# ProDocument_N64_SpyDVI_2024-08-21.net
KiCad netlist of a schematic drawn in EasyEDA Pro
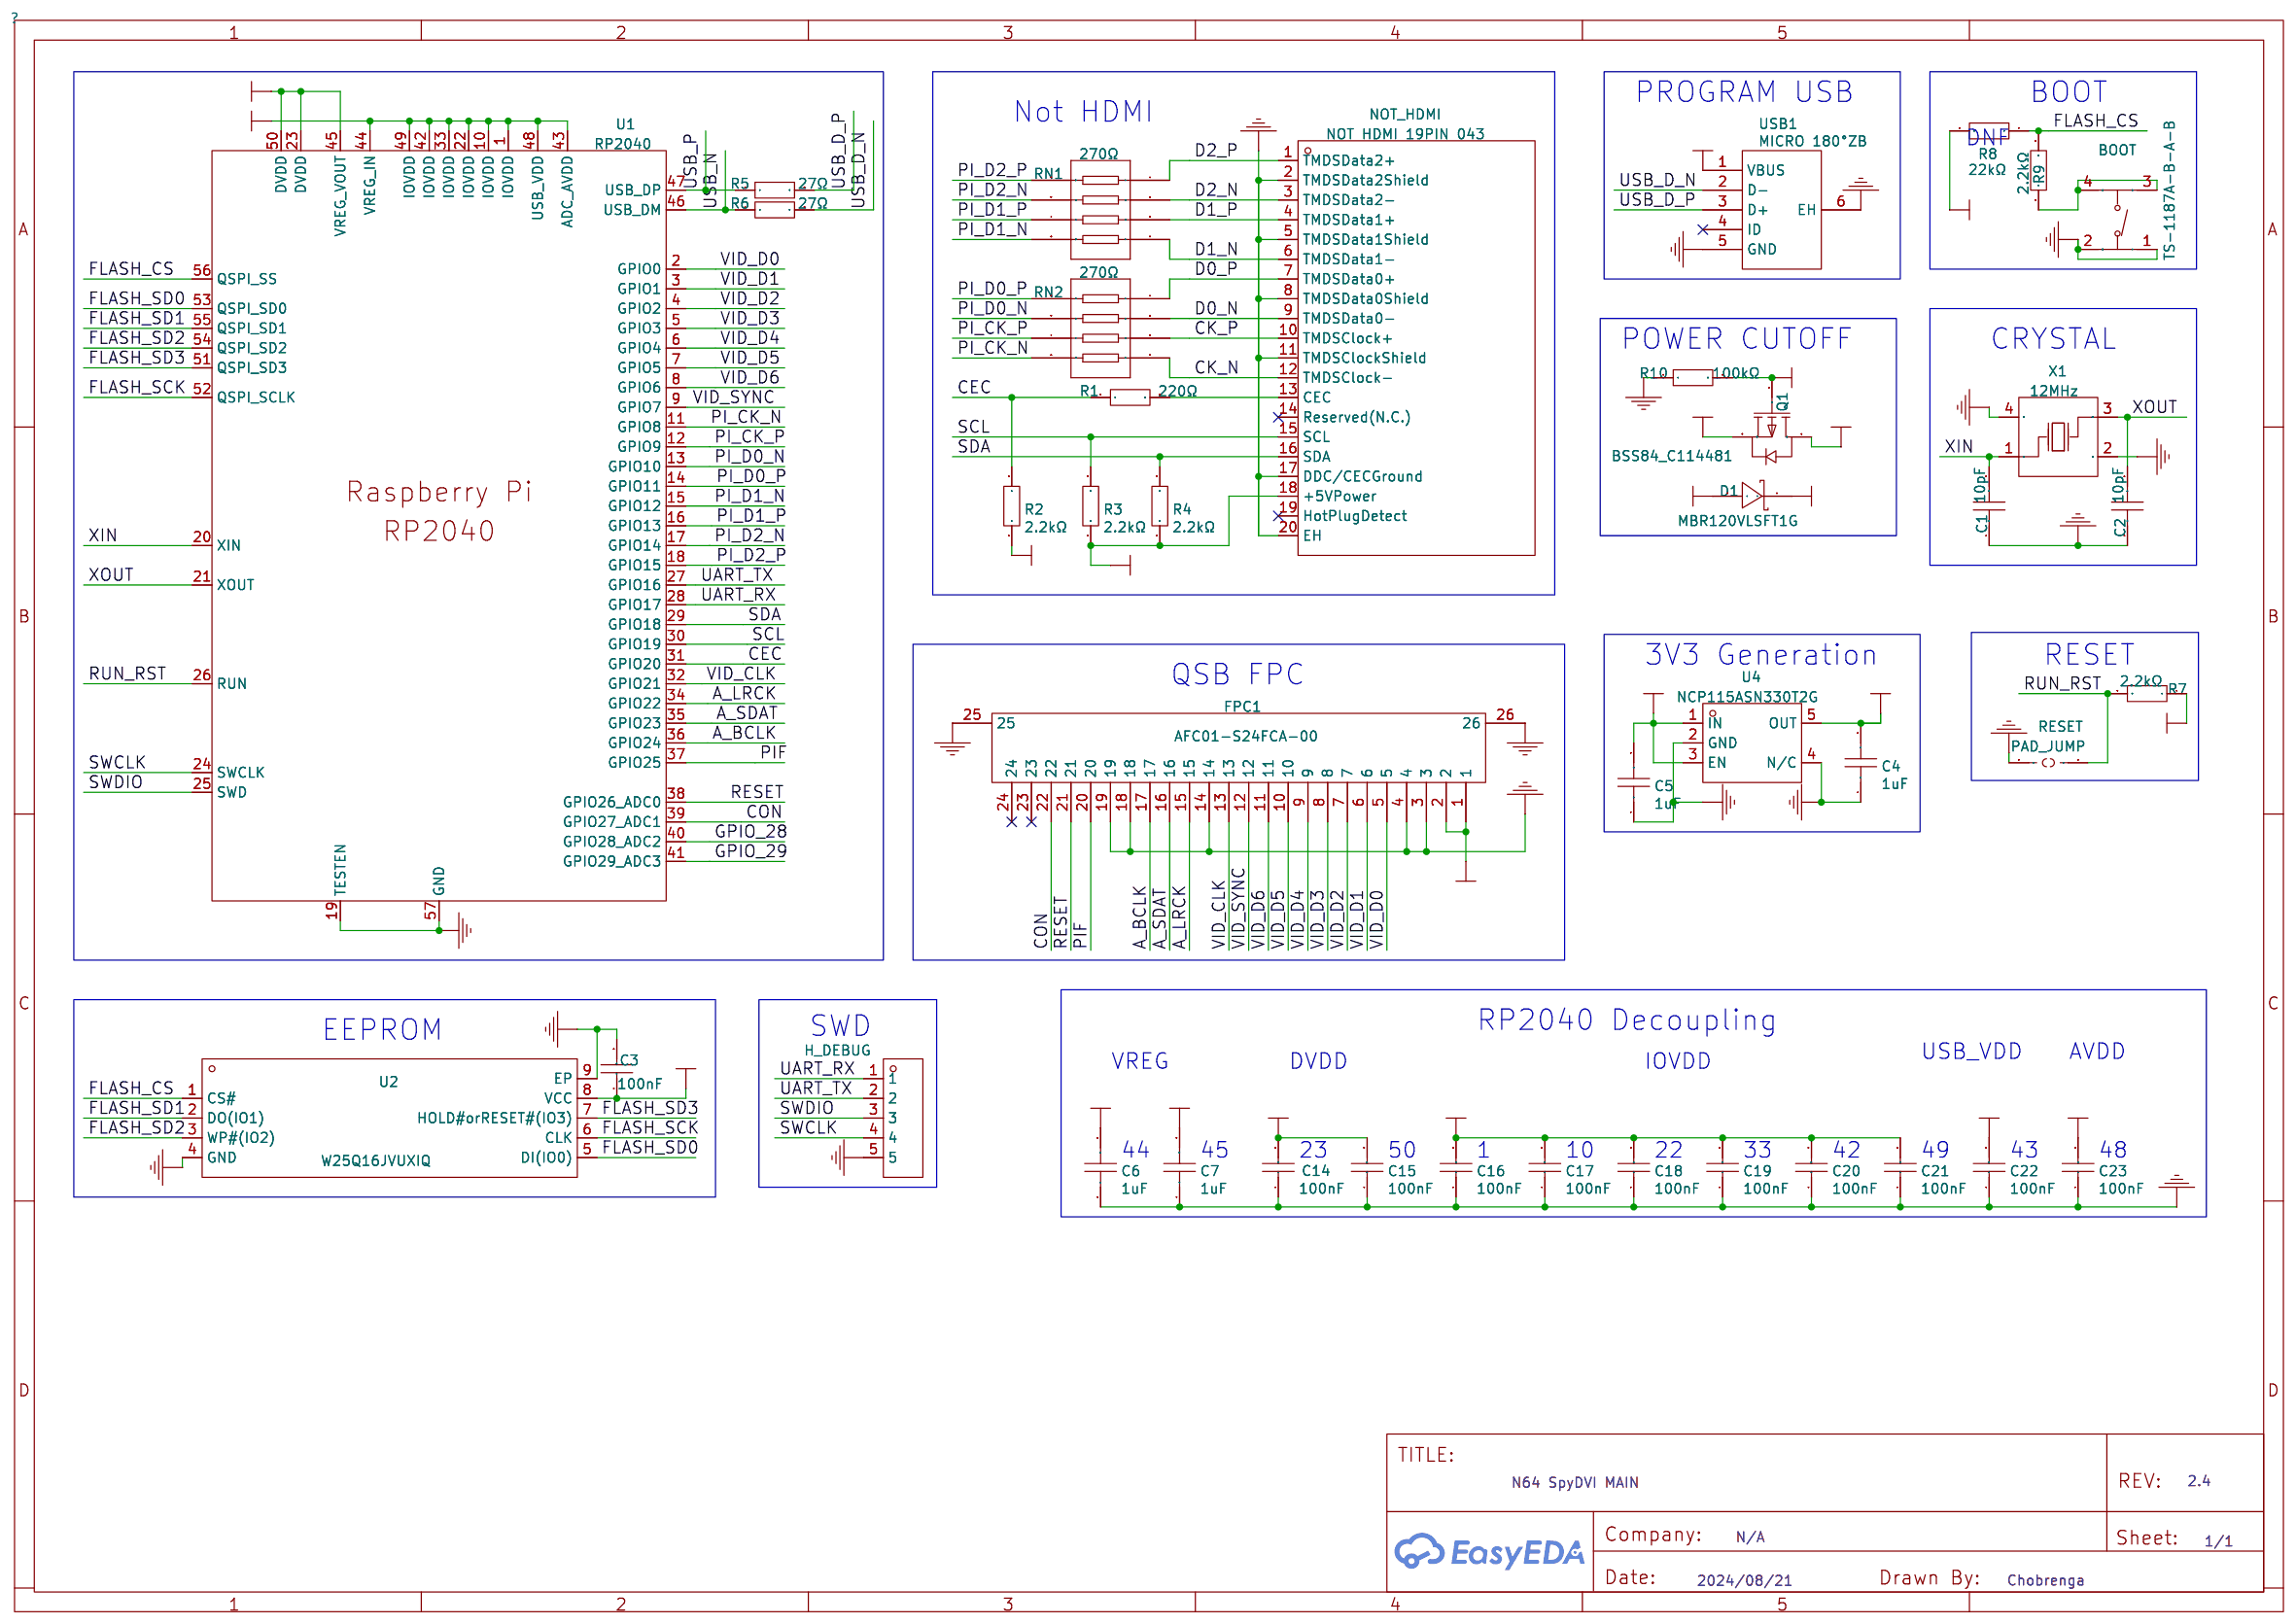
[diagram p0: schematic sheet]

(export (version "E")
  (design (tool "Eeschema 10.0.6"))
  (components
    (comp (ref "BOOT")
      (value "TS-1187A-B-A-B")
      (footprint "easyedapro:SW-SMD_4P-L5.1-W5.1-P3.70-LS6.5-TL-2")
      (fields (field (name "Manufacturer") "XKB Connectivity(中国星坤)"))
      (libsource (lib "easyedapro") (part "TS-1187A-B-A-B"))
    )
    (comp (ref "C1")
      (value "10pF")
      (footprint "easyedapro:C0402")
      (fields
        (field (name "Manufacturer Part") "CL05C100JB5NNNC")
        (field (name "Manufacturer") "SAMSUNG(三星)")
      )
      (libsource (lib "easyedapro") (part "10pF"))
    )
    (comp (ref "C2")
      (value "10pF")
      (footprint "easyedapro:C0402")
      (fields
        (field (name "Manufacturer Part") "CL05C100JB5NNNC")
        (field (name "Manufacturer") "SAMSUNG(三星)")
      )
      (libsource (lib "easyedapro") (part "10pF"))
    )
    (comp (ref "C3")
      (value "100nF")
      (footprint "easyedapro:C0402")
      (fields
        (field (name "Manufacturer Part") "CL05B104KO5NNNC")
        (field (name "Manufacturer") "SAMSUNG(三星)")
      )
      (libsource (lib "easyedapro") (part "100nF"))
    )
    (comp (ref "C4")
      (value "1uF")
      (footprint "easyedapro:C0402")
      (fields
        (field (name "Manufacturer Part") "CL05A105KA5NQNC")
        (field (name "Manufacturer") "SAMSUNG(三星)")
      )
      (libsource (lib "easyedapro") (part "1uF"))
    )
    (comp (ref "C5")
      (value "1uF")
      (footprint "easyedapro:C0402")
      (fields
        (field (name "Manufacturer Part") "CL05A105KA5NQNC")
        (field (name "Manufacturer") "SAMSUNG(三星)")
      )
      (libsource (lib "easyedapro") (part "1uF"))
    )
    (comp (ref "C6")
      (value "1uF")
      (footprint "easyedapro:C0402")
      (fields
        (field (name "Manufacturer Part") "CL05A105KA5NQNC")
        (field (name "Manufacturer") "SAMSUNG(三星)")
      )
      (libsource (lib "easyedapro") (part "1uF"))
    )
    (comp (ref "C7")
      (value "1uF")
      (footprint "easyedapro:C0402")
      (fields
        (field (name "Manufacturer Part") "CL05A105KA5NQNC")
        (field (name "Manufacturer") "SAMSUNG(三星)")
      )
      (libsource (lib "easyedapro") (part "1uF"))
    )
    (comp (ref "C14")
      (value "100nF")
      (footprint "easyedapro:C0402")
      (fields
        (field (name "Manufacturer Part") "CL05B104KO5NNNC")
        (field (name "Manufacturer") "SAMSUNG(三星)")
      )
      (libsource (lib "easyedapro") (part "100nF"))
    )
    (comp (ref "C15")
      (value "100nF")
      (footprint "easyedapro:C0402")
      (fields
        (field (name "Manufacturer Part") "CL05B104KO5NNNC")
        (field (name "Manufacturer") "SAMSUNG(三星)")
      )
      (libsource (lib "easyedapro") (part "100nF"))
    )
    (comp (ref "C16")
      (value "100nF")
      (footprint "easyedapro:C0402")
      (fields
        (field (name "Manufacturer Part") "CL05B104KO5NNNC")
        (field (name "Manufacturer") "SAMSUNG(三星)")
      )
      (libsource (lib "easyedapro") (part "100nF"))
    )
    (comp (ref "C17")
      (value "100nF")
      (footprint "easyedapro:C0402")
      (fields
        (field (name "Manufacturer Part") "CL05B104KO5NNNC")
        (field (name "Manufacturer") "SAMSUNG(三星)")
      )
      (libsource (lib "easyedapro") (part "100nF"))
    )
    (comp (ref "C18")
      (value "100nF")
      (footprint "easyedapro:C0402")
      (fields
        (field (name "Manufacturer Part") "CL05B104KO5NNNC")
        (field (name "Manufacturer") "SAMSUNG(三星)")
      )
      (libsource (lib "easyedapro") (part "100nF"))
    )
    (comp (ref "C19")
      (value "100nF")
      (footprint "easyedapro:C0402")
      (fields
        (field (name "Manufacturer Part") "CL05B104KO5NNNC")
        (field (name "Manufacturer") "SAMSUNG(三星)")
      )
      (libsource (lib "easyedapro") (part "100nF"))
    )
    (comp (ref "C20")
      (value "100nF")
      (footprint "easyedapro:C0402")
      (fields
        (field (name "Manufacturer Part") "CL05B104KO5NNNC")
        (field (name "Manufacturer") "SAMSUNG(三星)")
      )
      (libsource (lib "easyedapro") (part "100nF"))
    )
    (comp (ref "C21")
      (value "100nF")
      (footprint "easyedapro:C0402")
      (fields
        (field (name "Manufacturer Part") "CL05B104KO5NNNC")
        (field (name "Manufacturer") "SAMSUNG(三星)")
      )
      (libsource (lib "easyedapro") (part "100nF"))
    )
    (comp (ref "C22")
      (value "100nF")
      (footprint "easyedapro:C0402")
      (fields
        (field (name "Manufacturer Part") "CL05B104KO5NNNC")
        (field (name "Manufacturer") "SAMSUNG(三星)")
      )
      (libsource (lib "easyedapro") (part "100nF"))
    )
    (comp (ref "C23")
      (value "100nF")
      (footprint "easyedapro:C0402")
      (fields
        (field (name "Manufacturer Part") "CL05B104KO5NNNC")
        (field (name "Manufacturer") "SAMSUNG(三星)")
      )
      (libsource (lib "easyedapro") (part "100nF"))
    )
    (comp (ref "D1")
      (value "MBR120VLSFT1G")
      (footprint "easyedapro:SOD-123F_L2.8-W1.8-LS3.7-RD")
      (fields (field (name "Manufacturer") "onsemi(安森美)"))
      (libsource (lib "easyedapro") (part "MBR120VLSFT1G"))
    )
    (comp (ref "FPC1")
      (value "AFC01-S24FCA-00")
      (footprint "easyedapro:FPC-SMD_P0.50-24P_FGS-XJ-H2.0")
      (fields (field (name "Manufacturer") "JS(钜硕电子)"))
      (libsource (lib "easyedapro") (part "AFC01-S24FCA-00"))
    )
    (comp (ref "H_DEBUG")
      (value "PZ254V-11-05P")
      (footprint "easyedapro:HDR-TH_5P-P2.54-V-M")
      (fields (field (name "Manufacturer") "XFCN(兴飞)"))
      (libsource (lib "easyedapro") (part "PZ254V-11-05P"))
    )
    (comp (ref "NOT_HDMI")
      (value "NOT HDMI 19PIN 043")
      (footprint "easyedapro:HDMI-SMD_HDMI-19PIN-043")
      (fields
        (field (name "Manufacturer Part") "HDMI 19PIN 043")
        (field (name "Manufacturer") "SHOU HAN(首韩)")
      )
      (libsource (lib "easyedapro") (part "NOT HDMI 19PIN 043"))
    )
    (comp (ref "Q1")
      (value "BSS84_C114481")
      (footprint "easyedapro:SOT-23-3_L2.9-W1.6-P1.90-LS2.8-BR")
      (fields (field (name "Manufacturer Part") "BSS84") (field (name "Manufacturer") "CJ(江苏长电/长晶)"))
      (libsource (lib "easyedapro") (part "BSS84_C114481"))
    )
    (comp (ref "R1")
      (value "220Ω")
      (footprint "easyedapro:R0402")
      (fields
        (field (name "Manufacturer Part") "0402WGF2200TCE")
        (field (name "Manufacturer") "UNI-ROYAL(厚声)")
      )
      (libsource (lib "easyedapro") (part "220Ω"))
    )
    (comp (ref "R2")
      (value "2.2kΩ")
      (footprint "easyedapro:R0402")
      (fields
        (field (name "Manufacturer Part") "0402WGF2201TCE")
        (field (name "Manufacturer") "UNI-ROYAL(厚声)")
      )
      (libsource (lib "easyedapro") (part "2.2kΩ"))
    )
    (comp (ref "R3")
      (value "2.2kΩ")
      (footprint "easyedapro:R0402")
      (fields
        (field (name "Manufacturer Part") "0402WGF2201TCE")
        (field (name "Manufacturer") "UNI-ROYAL(厚声)")
      )
      (libsource (lib "easyedapro") (part "2.2kΩ"))
    )
    (comp (ref "R4")
      (value "2.2kΩ")
      (footprint "easyedapro:R0402")
      (fields
        (field (name "Manufacturer Part") "0402WGF2201TCE")
        (field (name "Manufacturer") "UNI-ROYAL(厚声)")
      )
      (libsource (lib "easyedapro") (part "2.2kΩ"))
    )
    (comp (ref "R5")
      (value "27Ω")
      (footprint "easyedapro:R0402")
      (fields
        (field (name "Manufacturer Part") "0402WGF270JTCE")
        (field (name "Manufacturer") "UNI-ROYAL(厚声)")
      )
      (libsource (lib "easyedapro") (part "27Ω"))
    )
    (comp (ref "R6")
      (value "27Ω")
      (footprint "easyedapro:R0402")
      (fields
        (field (name "Manufacturer Part") "0402WGF270JTCE")
        (field (name "Manufacturer") "UNI-ROYAL(厚声)")
      )
      (libsource (lib "easyedapro") (part "27Ω"))
    )
    (comp (ref "R7")
      (value "2.2kΩ")
      (footprint "easyedapro:R0402")
      (fields
        (field (name "Manufacturer Part") "0402WGF2201TCE")
        (field (name "Manufacturer") "UNI-ROYAL(厚声)")
      )
      (libsource (lib "easyedapro") (part "2.2kΩ"))
    )
    (comp (ref "R8")
      (value "22kΩ")
      (footprint "easyedapro:R0402")
      (libsource (lib "easyedapro") (part "22kΩ"))
    )
    (comp (ref "R9")
      (value "2.2kΩ")
      (footprint "easyedapro:R0402")
      (fields
        (field (name "Manufacturer Part") "0402WGF2201TCE")
        (field (name "Manufacturer") "UNI-ROYAL(厚声)")
      )
      (libsource (lib "easyedapro") (part "2.2kΩ"))
    )
    (comp (ref "R10")
      (value "100kΩ")
      (footprint "easyedapro:R0402")
      (fields
        (field (name "Manufacturer Part") "0402WGF1003TCE")
        (field (name "Manufacturer") "UNI-ROYAL(厚声)")
      )
      (libsource (lib "easyedapro") (part "100kΩ"))
    )
    (comp (ref "RESET")
      (value "PAD_JUMP")
      (footprint "easyedapro:PAD-JUMPER-2-NO_NO_SILK")
      (libsource (lib "easyedapro") (part "PAD_JUMP"))
    )
    (comp (ref "RN1")
      (value "270Ω")
      (footprint "easyedapro:RES-ARRAY-SMD_0804-8P-L2.0-W1.0-BL")
      (fields (field (name "Manufacturer Part") "CAT10-271J4LF") (field (name "Manufacturer") "BOURNS"))
      (libsource (lib "easyedapro") (part "270Ω"))
    )
    (comp (ref "RN2")
      (value "270Ω")
      (footprint "easyedapro:RES-ARRAY-SMD_0804-8P-L2.0-W1.0-BL")
      (fields (field (name "Manufacturer Part") "CAT10-271J4LF") (field (name "Manufacturer") "BOURNS"))
      (libsource (lib "easyedapro") (part "270Ω"))
    )
    (comp (ref "U1")
      (value "RP2040")
      (footprint "easyedapro:LQFN-56_L7.0-W7.0-P0.4-EP")
      (fields (field (name "Manufacturer") "Raspberry Pi(树莓派)"))
      (libsource (lib "easyedapro") (part "RP2040"))
    )
    (comp (ref "U2")
      (value "W25Q16JVUXIQ")
      (footprint "easyedapro:USON-8_L3.0-W2.0-P0.50-BL-EP")
      (fields (field (name "Manufacturer") "WINBOND(华邦)"))
      (libsource (lib "easyedapro") (part "W25Q16JVUXIQ"))
    )
    (comp (ref "U4")
      (value "NCP115ASN330T2G")
      (footprint "easyedapro:SOT-23-5_L3.0-W1.7-P0.95-LS2.8-BL")
      (fields (field (name "Manufacturer") "onsemi(安森美)"))
      (libsource (lib "easyedapro") (part "NCP115ASN330T2G"))
    )
    (comp (ref "USB1")
      (value "MICRO 180°ZB")
      (footprint "easyedapro:MICRO-USB-TH_MICRO-180-ZB")
      (fields (field (name "Manufacturer") "SHOU HAN(首韩)"))
      (libsource (lib "easyedapro") (part "MICRO 180°ZB"))
    )
    (comp (ref "X1")
      (value "12MHz")
      (footprint "easyedapro:CRYSTAL-SMD_4P-L3.2-W2.5-BL")
      (fields (field (name "Manufacturer Part") "X322512MMB4SI") (field (name "Manufacturer") "YXC(扬兴晶振)"))
      (libsource (lib "easyedapro") (part "12MHz"))
    )
  )
  (nets
    (net (code "1") (name "+1V1") (class "Default")
      (node (ref "C14") (pin "2") (pinfunction "2_2") (pintype "input"))
      (node (ref "C15") (pin "2") (pinfunction "2_2") (pintype "input"))
      (node (ref "C7") (pin "2") (pinfunction "2_2") (pintype "unspecified"))
      (node (ref "U1") (pin "23") (pinfunction "DVDD_23") (pintype "bidirectional"))
      (node (ref "U1") (pin "45") (pinfunction "VREG_VOUT_45") (pintype "bidirectional"))
      (node (ref "U1") (pin "50") (pinfunction "DVDD_50") (pintype "bidirectional"))
    )
    (net (code "2") (name "+3V3") (class "Default")
      (node (ref "C16") (pin "2") (pinfunction "2_2") (pintype "input"))
      (node (ref "C17") (pin "2") (pinfunction "2_2") (pintype "input"))
      (node (ref "C18") (pin "2") (pinfunction "2_2") (pintype "input"))
      (node (ref "C19") (pin "2") (pinfunction "2_2") (pintype "input"))
      (node (ref "C20") (pin "2") (pinfunction "2_2") (pintype "input"))
      (node (ref "C21") (pin "2") (pinfunction "2_2") (pintype "input"))
      (node (ref "C22") (pin "2") (pinfunction "2_2") (pintype "input"))
      (node (ref "C23") (pin "2") (pinfunction "2_2") (pintype "input"))
      (node (ref "C3") (pin "1") (pinfunction "1_1") (pintype "input"))
      (node (ref "C4") (pin "2") (pinfunction "2_2") (pintype "unspecified"))
      (node (ref "C6") (pin "2") (pinfunction "2_2") (pintype "unspecified"))
      (node (ref "R2") (pin "1") (pinfunction "1_1") (pintype "input"))
      (node (ref "R7") (pin "1") (pinfunction "1_1") (pintype "input"))
      (node (ref "R8") (pin "2") (pinfunction "2_2") (pintype "input"))
      (node (ref "U1") (pin "1") (pinfunction "IOVDD_1") (pintype "bidirectional"))
      (node (ref "U1") (pin "10") (pinfunction "IOVDD_10") (pintype "bidirectional"))
      (node (ref "U1") (pin "22") (pinfunction "IOVDD_22") (pintype "bidirectional"))
      (node (ref "U1") (pin "33") (pinfunction "IOVDD_33") (pintype "bidirectional"))
      (node (ref "U1") (pin "42") (pinfunction "IOVDD_42") (pintype "bidirectional"))
      (node (ref "U1") (pin "43") (pinfunction "ADC_AVDD_43") (pintype "bidirectional"))
      (node (ref "U1") (pin "44") (pinfunction "VREG_IN_44") (pintype "bidirectional"))
      (node (ref "U1") (pin "48") (pinfunction "USB_VDD_48") (pintype "bidirectional"))
      (node (ref "U1") (pin "49") (pinfunction "IOVDD_49") (pintype "bidirectional"))
      (node (ref "U2") (pin "8") (pinfunction "VCC_8") (pintype "unspecified"))
      (node (ref "U4") (pin "5") (pinfunction "OUT_5") (pintype "unspecified"))
    )
    (net (code "3") (name "+5V_N64") (class "Default")
      (node (ref "FPC1") (pin "1") (pinfunction "1_1") (pintype "unspecified"))
      (node (ref "FPC1") (pin "2") (pinfunction "2_2") (pintype "unspecified"))
      (node (ref "Q1") (pin "3") (pinfunction "D_3") (pintype "unspecified"))
    )
    (net (code "4") (name "+VBUS") (class "Default")
      (node (ref "D1") (pin "2") (pinfunction "A_2") (pintype "unspecified"))
      (node (ref "Q1") (pin "1") (pinfunction "G_1") (pintype "unspecified"))
      (node (ref "R10") (pin "2") (pinfunction "2_2") (pintype "input"))
      (node (ref "USB1") (pin "1") (pinfunction "VBUS_1") (pintype "unspecified"))
    )
    (net (code "5") (name "+VSYS") (class "Default")
      (node (ref "C5") (pin "2") (pinfunction "2_2") (pintype "unspecified"))
      (node (ref "D1") (pin "1") (pinfunction "K_1") (pintype "unspecified"))
      (node (ref "NOT_HDMI") (pin "18") (pinfunction "+5VPower_18") (pintype "unspecified"))
      (node (ref "Q1") (pin "2") (pinfunction "S_2") (pintype "unspecified"))
      (node (ref "R3") (pin "1") (pinfunction "1_1") (pintype "input"))
      (node (ref "R4") (pin "1") (pinfunction "1_1") (pintype "input"))
      (node (ref "U4") (pin "1") (pinfunction "IN_1") (pintype "unspecified"))
      (node (ref "U4") (pin "3") (pinfunction "EN_3") (pintype "unspecified"))
    )
    (net (code "6") (name "/A_BCLK") (class "Default")
      (node (ref "FPC1") (pin "17") (pinfunction "17_17") (pintype "unspecified"))
      (node (ref "U1") (pin "36") (pinfunction "GPIO24_36") (pintype "bidirectional"))
    )
    (net (code "7") (name "/A_LRCK") (class "Default")
      (node (ref "FPC1") (pin "15") (pinfunction "15_15") (pintype "unspecified"))
      (node (ref "U1") (pin "34") (pinfunction "GPIO22_34") (pintype "bidirectional"))
    )
    (net (code "8") (name "/A_SDAT") (class "Default")
      (node (ref "FPC1") (pin "16") (pinfunction "16_16") (pintype "unspecified"))
      (node (ref "U1") (pin "35") (pinfunction "GPIO23_35") (pintype "bidirectional"))
    )
    (net (code "9") (name "/CEC") (class "Default")
      (node (ref "R1") (pin "1") (pinfunction "1_1") (pintype "input"))
      (node (ref "R2") (pin "2") (pinfunction "2_2") (pintype "input"))
      (node (ref "U1") (pin "31") (pinfunction "GPIO20_31") (pintype "bidirectional"))
    )
    (net (code "10") (name "/CK_N") (class "Default")
      (node (ref "NOT_HDMI") (pin "12") (pinfunction "TMDSClock-_12") (pintype "unspecified"))
      (node (ref "RN2") (pin "1") (pinfunction "1_1") (pintype "input"))
    )
    (net (code "11") (name "/CK_P") (class "Default")
      (node (ref "NOT_HDMI") (pin "10") (pinfunction "TMDSClock+_10") (pintype "unspecified"))
      (node (ref "RN2") (pin "2") (pinfunction "2_2") (pintype "input"))
    )
    (net (code "12") (name "/CON") (class "Default")
      (node (ref "FPC1") (pin "22") (pinfunction "22_22") (pintype "unspecified"))
      (node (ref "U1") (pin "39") (pinfunction "GPIO27_ADC1_39") (pintype "bidirectional"))
    )
    (net (code "13") (name "/D0_N") (class "Default")
      (node (ref "NOT_HDMI") (pin "9") (pinfunction "TMDSData0-_9") (pintype "unspecified"))
      (node (ref "RN2") (pin "3") (pinfunction "3_3") (pintype "input"))
    )
    (net (code "14") (name "/D0_P") (class "Default")
      (node (ref "NOT_HDMI") (pin "7") (pinfunction "TMDSData0+_7") (pintype "unspecified"))
      (node (ref "RN2") (pin "4") (pinfunction "4_4") (pintype "input"))
    )
    (net (code "15") (name "/D1_N") (class "Default")
      (node (ref "NOT_HDMI") (pin "6") (pinfunction "TMDSData1-_6") (pintype "unspecified"))
      (node (ref "RN1") (pin "1") (pinfunction "1_1") (pintype "input"))
    )
    (net (code "16") (name "/D1_P") (class "Default")
      (node (ref "NOT_HDMI") (pin "4") (pinfunction "TMDSData1+_4") (pintype "unspecified"))
      (node (ref "RN1") (pin "2") (pinfunction "2_2") (pintype "input"))
    )
    (net (code "17") (name "/D2_N") (class "Default")
      (node (ref "NOT_HDMI") (pin "3") (pinfunction "TMDSData2-_3") (pintype "unspecified"))
      (node (ref "RN1") (pin "3") (pinfunction "3_3") (pintype "input"))
    )
    (net (code "18") (name "/D2_P") (class "Default")
      (node (ref "NOT_HDMI") (pin "1") (pinfunction "TMDSData2+_1") (pintype "unspecified"))
      (node (ref "RN1") (pin "4") (pinfunction "4_4") (pintype "input"))
    )
    (net (code "19") (name "/FLASH_CS") (class "Default")
      (node (ref "R8") (pin "1") (pinfunction "1_1") (pintype "input"))
      (node (ref "R9") (pin "2") (pinfunction "2_2") (pintype "input"))
      (node (ref "U1") (pin "56") (pinfunction "QSPI_SS_56") (pintype "bidirectional"))
      (node (ref "U2") (pin "1") (pinfunction "CS#_1") (pintype "unspecified"))
    )
    (net (code "20") (name "/FLASH_SCK") (class "Default")
      (node (ref "U1") (pin "52") (pinfunction "QSPI_SCLK_52") (pintype "output"))
      (node (ref "U2") (pin "6") (pinfunction "CLK_6") (pintype "unspecified"))
    )
    (net (code "21") (name "/FLASH_SD0") (class "Default")
      (node (ref "U1") (pin "53") (pinfunction "QSPI_SD0_53") (pintype "bidirectional"))
      (node (ref "U2") (pin "5") (pinfunction "DI(IO0)_5") (pintype "unspecified"))
    )
    (net (code "22") (name "/FLASH_SD1") (class "Default")
      (node (ref "U1") (pin "55") (pinfunction "QSPI_SD1_55") (pintype "bidirectional"))
      (node (ref "U2") (pin "2") (pinfunction "DO(IO1)_2") (pintype "unspecified"))
    )
    (net (code "23") (name "/FLASH_SD2") (class "Default")
      (node (ref "U1") (pin "54") (pinfunction "QSPI_SD2_54") (pintype "bidirectional"))
      (node (ref "U2") (pin "3") (pinfunction "WP#(IO2)_3") (pintype "unspecified"))
    )
    (net (code "24") (name "/FLASH_SD3") (class "Default")
      (node (ref "U1") (pin "51") (pinfunction "QSPI_SD3_51") (pintype "bidirectional"))
      (node (ref "U2") (pin "7") (pinfunction "HOLD#orRESET#(IO3)_7") (pintype "unspecified"))
    )
    (net (code "25") (name "/GPIO_28") (class "Default")
      (node (ref "U1") (pin "40") (pinfunction "GPIO28_ADC2_40") (pintype "bidirectional"))
    )
    (net (code "26") (name "/GPIO_29") (class "Default")
      (node (ref "U1") (pin "41") (pinfunction "GPIO29_ADC3_41") (pintype "bidirectional"))
    )
    (net (code "27") (name "/PIF") (class "Default")
      (node (ref "FPC1") (pin "20") (pinfunction "20_20") (pintype "unspecified"))
      (node (ref "U1") (pin "37") (pinfunction "GPIO25_37") (pintype "bidirectional"))
    )
    (net (code "28") (name "/PI_CK_N") (class "Default")
      (node (ref "RN2") (pin "8") (pinfunction "8_8") (pintype "input"))
      (node (ref "U1") (pin "11") (pinfunction "GPIO8_11") (pintype "bidirectional"))
    )
    (net (code "29") (name "/PI_CK_P") (class "Default")
      (node (ref "RN2") (pin "7") (pinfunction "7_7") (pintype "input"))
      (node (ref "U1") (pin "12") (pinfunction "GPIO9_12") (pintype "bidirectional"))
    )
    (net (code "30") (name "/PI_D0_N") (class "Default")
      (node (ref "RN2") (pin "6") (pinfunction "6_6") (pintype "input"))
      (node (ref "U1") (pin "13") (pinfunction "GPIO10_13") (pintype "bidirectional"))
    )
    (net (code "31") (name "/PI_D0_P") (class "Default")
      (node (ref "RN2") (pin "5") (pinfunction "5_5") (pintype "input"))
      (node (ref "U1") (pin "14") (pinfunction "GPIO11_14") (pintype "bidirectional"))
    )
    (net (code "32") (name "/PI_D1_N") (class "Default")
      (node (ref "RN1") (pin "8") (pinfunction "8_8") (pintype "input"))
      (node (ref "U1") (pin "15") (pinfunction "GPIO12_15") (pintype "bidirectional"))
    )
    (net (code "33") (name "/PI_D1_P") (class "Default")
      (node (ref "RN1") (pin "7") (pinfunction "7_7") (pintype "input"))
      (node (ref "U1") (pin "16") (pinfunction "GPIO13_16") (pintype "bidirectional"))
    )
    (net (code "34") (name "/PI_D2_N") (class "Default")
      (node (ref "RN1") (pin "6") (pinfunction "6_6") (pintype "input"))
      (node (ref "U1") (pin "17") (pinfunction "GPIO14_17") (pintype "bidirectional"))
    )
    (net (code "35") (name "/PI_D2_P") (class "Default")
      (node (ref "RN1") (pin "5") (pinfunction "5_5") (pintype "input"))
      (node (ref "U1") (pin "18") (pinfunction "GPIO15_18") (pintype "bidirectional"))
    )
    (net (code "36") (name "/RESET") (class "Default")
      (node (ref "FPC1") (pin "21") (pinfunction "21_21") (pintype "unspecified"))
      (node (ref "U1") (pin "38") (pinfunction "GPIO26_ADC0_38") (pintype "bidirectional"))
    )
    (net (code "37") (name "/RUN_RST") (class "Default")
      (node (ref "R7") (pin "2") (pinfunction "2_2") (pintype "input"))
      (node (ref "RESET") (pin "2") (pinfunction "2_2") (pintype "unspecified"))
      (node (ref "U1") (pin "26") (pinfunction "RUN_26") (pintype "input"))
    )
    (net (code "38") (name "/SCL") (class "Default")
      (node (ref "NOT_HDMI") (pin "15") (pinfunction "SCL_15") (pintype "unspecified"))
      (node (ref "R3") (pin "2") (pinfunction "2_2") (pintype "input"))
      (node (ref "U1") (pin "30") (pinfunction "GPIO19_30") (pintype "bidirectional"))
    )
    (net (code "39") (name "/SDA") (class "Default")
      (node (ref "NOT_HDMI") (pin "16") (pinfunction "SDA_16") (pintype "unspecified"))
      (node (ref "R4") (pin "2") (pinfunction "2_2") (pintype "input"))
      (node (ref "U1") (pin "29") (pinfunction "GPIO18_29") (pintype "bidirectional"))
    )
    (net (code "40") (name "/SWCLK") (class "Default")
      (node (ref "H_DEBUG") (pin "4") (pinfunction "4_4") (pintype "unspecified"))
      (node (ref "U1") (pin "24") (pinfunction "SWCLK_24") (pintype "output"))
    )
    (net (code "41") (name "/SWDIO") (class "Default")
      (node (ref "H_DEBUG") (pin "3") (pinfunction "3_3") (pintype "unspecified"))
      (node (ref "U1") (pin "25") (pinfunction "SWD_25") (pintype "bidirectional"))
    )
    (net (code "42") (name "/UART_RX") (class "Default")
      (node (ref "H_DEBUG") (pin "1") (pinfunction "1_1") (pintype "unspecified"))
      (node (ref "U1") (pin "28") (pinfunction "GPIO17_28") (pintype "bidirectional"))
    )
    (net (code "43") (name "/UART_TX") (class "Default")
      (node (ref "H_DEBUG") (pin "2") (pinfunction "2_2") (pintype "unspecified"))
      (node (ref "U1") (pin "27") (pinfunction "GPIO16_27") (pintype "bidirectional"))
    )
    (net (code "44") (name "/USB_D_N") (class "Default")
      (node (ref "R6") (pin "2") (pinfunction "2_2") (pintype "input"))
      (node (ref "USB1") (pin "2") (pinfunction "D-_2") (pintype "unspecified"))
    )
    (net (code "45") (name "/USB_D_P") (class "Default")
      (node (ref "R5") (pin "2") (pinfunction "2_2") (pintype "input"))
      (node (ref "USB1") (pin "3") (pinfunction "D+_3") (pintype "unspecified"))
    )
    (net (code "46") (name "/USB_N") (class "Default")
      (node (ref "R6") (pin "1") (pinfunction "1_1") (pintype "input"))
      (node (ref "U1") (pin "46") (pinfunction "USB_DM_46") (pintype "bidirectional"))
    )
    (net (code "47") (name "/USB_P") (class "Default")
      (node (ref "R5") (pin "1") (pinfunction "1_1") (pintype "input"))
      (node (ref "U1") (pin "47") (pinfunction "USB_DP_47") (pintype "bidirectional"))
    )
    (net (code "48") (name "/VID_CLK") (class "Default")
      (node (ref "FPC1") (pin "13") (pinfunction "13_13") (pintype "unspecified"))
      (node (ref "U1") (pin "32") (pinfunction "GPIO21_32") (pintype "bidirectional"))
    )
    (net (code "49") (name "/VID_D0") (class "Default")
      (node (ref "FPC1") (pin "5") (pinfunction "5_5") (pintype "unspecified"))
      (node (ref "U1") (pin "2") (pinfunction "GPIO0_2") (pintype "bidirectional"))
    )
    (net (code "50") (name "/VID_D1") (class "Default")
      (node (ref "FPC1") (pin "6") (pinfunction "6_6") (pintype "unspecified"))
      (node (ref "U1") (pin "3") (pinfunction "GPIO1_3") (pintype "bidirectional"))
    )
    (net (code "51") (name "/VID_D2") (class "Default")
      (node (ref "FPC1") (pin "7") (pinfunction "7_7") (pintype "unspecified"))
      (node (ref "U1") (pin "4") (pinfunction "GPIO2_4") (pintype "bidirectional"))
    )
    (net (code "52") (name "/VID_D3") (class "Default")
      (node (ref "FPC1") (pin "8") (pinfunction "8_8") (pintype "unspecified"))
      (node (ref "U1") (pin "5") (pinfunction "GPIO3_5") (pintype "bidirectional"))
    )
    (net (code "53") (name "/VID_D4") (class "Default")
      (node (ref "FPC1") (pin "9") (pinfunction "9_9") (pintype "unspecified"))
      (node (ref "U1") (pin "6") (pinfunction "GPIO4_6") (pintype "bidirectional"))
    )
    (net (code "54") (name "/VID_D5") (class "Default")
      (node (ref "FPC1") (pin "10") (pinfunction "10_10") (pintype "unspecified"))
      (node (ref "U1") (pin "7") (pinfunction "GPIO5_7") (pintype "bidirectional"))
    )
    (net (code "55") (name "/VID_D6") (class "Default")
      (node (ref "FPC1") (pin "11") (pinfunction "11_11") (pintype "unspecified"))
      (node (ref "U1") (pin "8") (pinfunction "GPIO6_8") (pintype "bidirectional"))
    )
    (net (code "56") (name "/VID_SYNC") (class "Default")
      (node (ref "FPC1") (pin "12") (pinfunction "12_12") (pintype "unspecified"))
      (node (ref "U1") (pin "9") (pinfunction "GPIO7_9") (pintype "bidirectional"))
    )
    (net (code "57") (name "/XIN") (class "Default")
      (node (ref "C1") (pin "2") (pinfunction "2_2") (pintype "unspecified"))
      (node (ref "U1") (pin "20") (pinfunction "XIN_20") (pintype "input"))
      (node (ref "X1") (pin "1") (pinfunction "OSC1_1") (pintype "unspecified"))
    )
    (net (code "58") (name "/XOUT") (class "Default")
      (node (ref "C2") (pin "2") (pinfunction "2_2") (pintype "unspecified"))
      (node (ref "U1") (pin "21") (pinfunction "XOUT_21") (pintype "unspecified"))
      (node (ref "X1") (pin "3") (pinfunction "OSC2_3") (pintype "unspecified"))
    )
    (net (code "59") (name "GND") (class "Default")
      (node (ref "BOOT") (pin "1") (pinfunction "A_1") (pintype "unspecified"))
      (node (ref "BOOT") (pin "2") (pinfunction "B_2") (pintype "unspecified"))
      (node (ref "C1") (pin "1") (pinfunction "1_1") (pintype "unspecified"))
      (node (ref "C14") (pin "1") (pinfunction "1_1") (pintype "input"))
      (node (ref "C15") (pin "1") (pinfunction "1_1") (pintype "input"))
      (node (ref "C16") (pin "1") (pinfunction "1_1") (pintype "input"))
      (node (ref "C17") (pin "1") (pinfunction "1_1") (pintype "input"))
      (node (ref "C18") (pin "1") (pinfunction "1_1") (pintype "input"))
      (node (ref "C19") (pin "1") (pinfunction "1_1") (pintype "input"))
      (node (ref "C2") (pin "1") (pinfunction "1_1") (pintype "unspecified"))
      (node (ref "C20") (pin "1") (pinfunction "1_1") (pintype "input"))
      (node (ref "C21") (pin "1") (pinfunction "1_1") (pintype "input"))
      (node (ref "C22") (pin "1") (pinfunction "1_1") (pintype "input"))
      (node (ref "C23") (pin "1") (pinfunction "1_1") (pintype "input"))
      (node (ref "C3") (pin "2") (pinfunction "2_2") (pintype "input"))
      (node (ref "C4") (pin "1") (pinfunction "1_1") (pintype "unspecified"))
      (node (ref "C5") (pin "1") (pinfunction "1_1") (pintype "unspecified"))
      (node (ref "C6") (pin "1") (pinfunction "1_1") (pintype "unspecified"))
      (node (ref "C7") (pin "1") (pinfunction "1_1") (pintype "unspecified"))
      (node (ref "FPC1") (pin "14") (pinfunction "14_14") (pintype "unspecified"))
      (node (ref "FPC1") (pin "18") (pinfunction "18_18") (pintype "unspecified"))
      (node (ref "FPC1") (pin "19") (pinfunction "19_19") (pintype "unspecified"))
      (node (ref "FPC1") (pin "25") (pinfunction "25_25") (pintype "unspecified"))
      (node (ref "FPC1") (pin "26") (pinfunction "26_26") (pintype "unspecified"))
      (node (ref "FPC1") (pin "3") (pinfunction "3_3") (pintype "unspecified"))
      (node (ref "FPC1") (pin "4") (pinfunction "4_4") (pintype "unspecified"))
      (node (ref "H_DEBUG") (pin "5") (pinfunction "5_5") (pintype "unspecified"))
      (node (ref "NOT_HDMI") (pin "11") (pinfunction "TMDSClockShield_11") (pintype "unspecified"))
      (node (ref "NOT_HDMI") (pin "17") (pinfunction "DDC/CECGround_17") (pintype "unspecified"))
      (node (ref "NOT_HDMI") (pin "2") (pinfunction "TMDSData2Shield_2") (pintype "unspecified"))
      (node (ref "NOT_HDMI") (pin "20") (pinfunction "EH_20") (pintype "unspecified"))
      (node (ref "NOT_HDMI") (pin "5") (pinfunction "TMDSData1Shield_5") (pintype "unspecified"))
      (node (ref "NOT_HDMI") (pin "8") (pinfunction "TMDSData0Shield_8") (pintype "unspecified"))
      (node (ref "R10") (pin "1") (pinfunction "1_1") (pintype "input"))
      (node (ref "RESET") (pin "1") (pinfunction "1_1") (pintype "unspecified"))
      (node (ref "U1") (pin "19") (pinfunction "TESTEN_19") (pintype "unspecified"))
      (node (ref "U1") (pin "57") (pinfunction "GND_57") (pintype "bidirectional"))
      (node (ref "U2") (pin "4") (pinfunction "GND_4") (pintype "unspecified"))
      (node (ref "U2") (pin "9") (pinfunction "EP_9") (pintype "unspecified"))
      (node (ref "U4") (pin "2") (pinfunction "GND_2") (pintype "unspecified"))
      (node (ref "U4") (pin "4") (pinfunction "N/C_4") (pintype "unspecified"))
      (node (ref "USB1") (pin "5") (pinfunction "GND_5") (pintype "unspecified"))
      (node (ref "USB1") (pin "6") (pinfunction "EH_6") (pintype "unspecified"))
      (node (ref "X1") (pin "2") (pinfunction "GND_2") (pintype "unspecified"))
      (node (ref "X1") (pin "4") (pinfunction "GND_4") (pintype "unspecified"))
    )
    (net (code "60") (name "Net-(BOOT-C)") (class "Default")
      (node (ref "BOOT") (pin "3") (pinfunction "C_3") (pintype "unspecified"))
      (node (ref "BOOT") (pin "4") (pinfunction "D_4") (pintype "unspecified"))
      (node (ref "R9") (pin "1") (pinfunction "1_1") (pintype "input"))
    )
    (net (code "61") (name "Net-(NOT_HDMI-CEC)") (class "Default")
      (node (ref "NOT_HDMI") (pin "13") (pinfunction "CEC_13") (pintype "unspecified"))
      (node (ref "R1") (pin "2") (pinfunction "2_2") (pintype "input"))
    )
    (net (code "62") (name "unconnected-(FPC1-Pad23)") (class "Default")
      (node (ref "FPC1") (pin "23") (pinfunction "23_23") (pintype "unspecified+no_connect"))
    )
    (net (code "63") (name "unconnected-(FPC1-Pad24)") (class "Default")
      (node (ref "FPC1") (pin "24") (pinfunction "24_24") (pintype "unspecified+no_connect"))
    )
    (net (code "64") (name "unconnected-(NOT_HDMI-HotPlugDetect-Pad19)") (class "Default")
      (node (ref "NOT_HDMI") (pin "19") (pinfunction "HotPlugDetect_19") (pintype "unspecified+no_connect"))
    )
    (net (code "65") (name "unconnected-(NOT_HDMI-Reserved(N.C.)-Pad14)") (class "Default")
      (node (ref "NOT_HDMI") (pin "14") (pinfunction "Reserved(N.C.)_14") (pintype "unspecified+no_connect"))
    )
    (net (code "66") (name "unconnected-(USB1-ID-Pad4)") (class "Default")
      (node (ref "USB1") (pin "4") (pinfunction "ID_4") (pintype "unspecified+no_connect"))
    )
  )
)
